# MMMM_Top.net
KiCad netlist of a schematic drawn in EAGLE
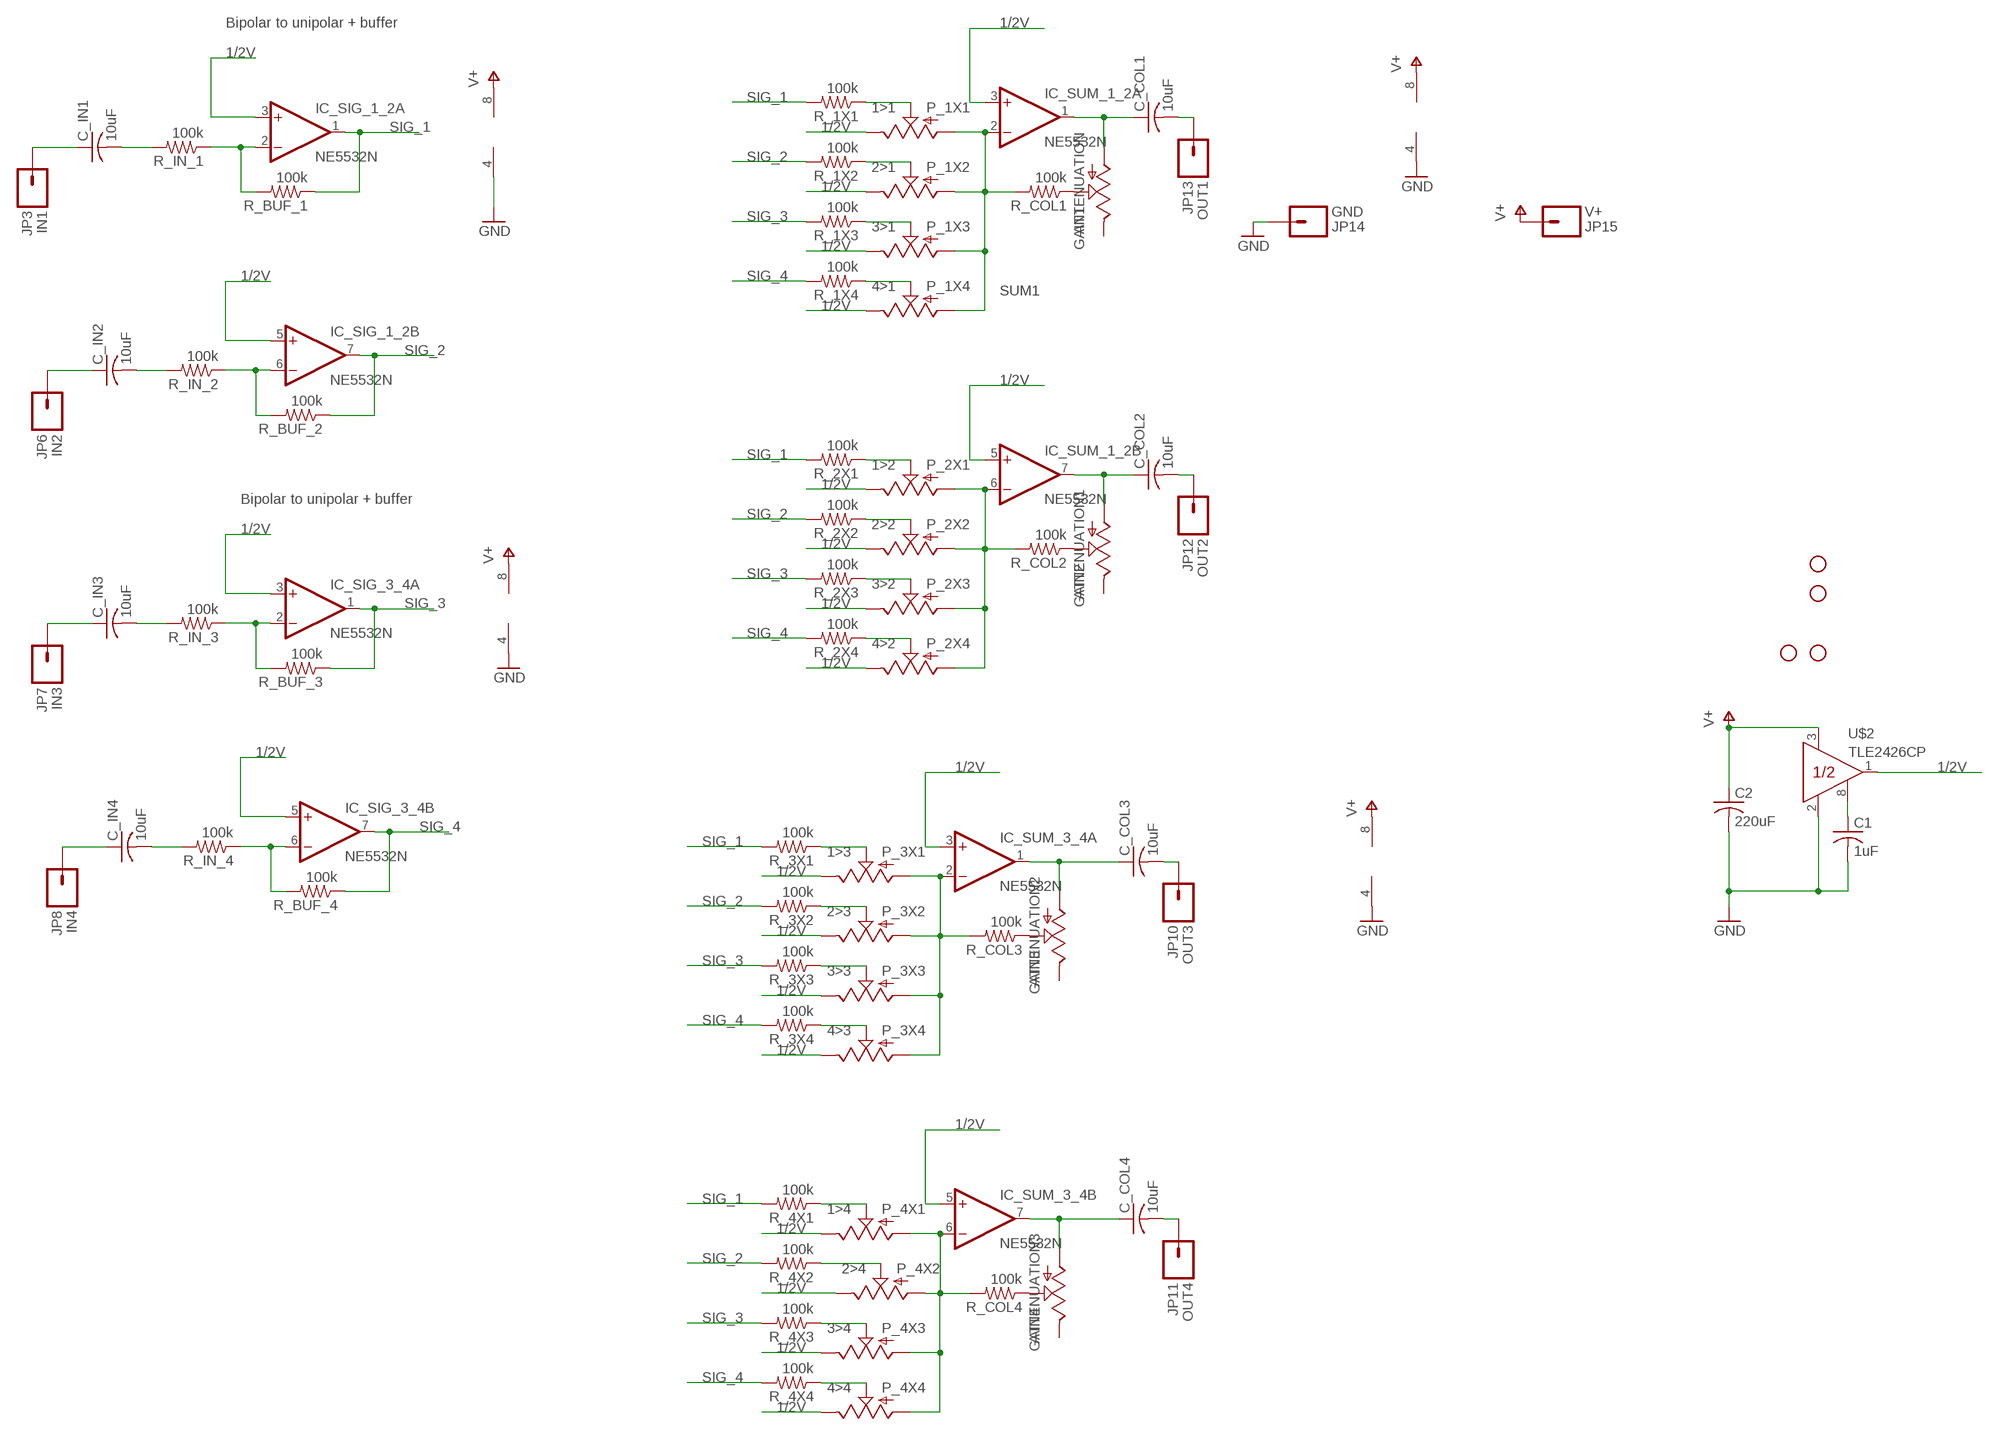
[diagram p0: schematic, sheet 1]

(export (version "E")
  (design (tool "Eeschema 10.0.6"))
  (components
    (comp (ref "ATTENUATION")
      (value "GAIN1")
      (footprint "eagle-import:TRIM_POT")
      (libsource (lib "eagle-import") (part "POTTRIM"))
    )
    (comp (ref "ATTENUATION1")
      (value "GAIN2")
      (footprint "eagle-import:TRIM_POT")
      (libsource (lib "eagle-import") (part "POTTRIM"))
    )
    (comp (ref "ATTENUATION2")
      (value "GAIN3")
      (footprint "eagle-import:TRIM_POT")
      (libsource (lib "eagle-import") (part "POTTRIM"))
    )
    (comp (ref "ATTENUATION3")
      (value "GAIN4")
      (footprint "eagle-import:TRIM_POT")
      (libsource (lib "eagle-import") (part "POTTRIM"))
    )
    (comp (ref "C1")
      (value "1uF")
      (footprint "eagle-import:C025-030X050")
      (libsource (lib "eagle-import") (part "C-US025-030X050"))
    )
    (comp (ref "C2")
      (value "220uF")
      (footprint "eagle-import:C050-075X075")
      (libsource (lib "eagle-import") (part "C-US050-075X075"))
    )
    (comp (ref "C_COL1")
      (value "10uF")
      (footprint "eagle-import:C025-025X050")
      (libsource (lib "eagle-import") (part "C-US025-025X050"))
    )
    (comp (ref "C_COL2")
      (value "10uF")
      (footprint "eagle-import:C025-025X050")
      (libsource (lib "eagle-import") (part "C-US025-025X050"))
    )
    (comp (ref "C_COL3")
      (value "10uF")
      (footprint "eagle-import:C025-025X050")
      (libsource (lib "eagle-import") (part "C-US025-025X050"))
    )
    (comp (ref "C_COL4")
      (value "10uF")
      (footprint "eagle-import:C025-025X050")
      (libsource (lib "eagle-import") (part "C-US025-025X050"))
    )
    (comp (ref "C_IN1")
      (value "10uF")
      (footprint "eagle-import:C025-025X050")
      (libsource (lib "eagle-import") (part "C-US025-025X050"))
    )
    (comp (ref "C_IN2")
      (value "10uF")
      (footprint "eagle-import:C025-025X050")
      (libsource (lib "eagle-import") (part "C-US025-025X050"))
    )
    (comp (ref "C_IN3")
      (value "10uF")
      (footprint "eagle-import:C025-025X050")
      (libsource (lib "eagle-import") (part "C-US025-025X050"))
    )
    (comp (ref "C_IN4")
      (value "10uF")
      (footprint "eagle-import:C025-025X050")
      (libsource (lib "eagle-import") (part "C-US025-025X050"))
    )
    (comp (ref "IC_SIG_1_2")
      (value "NE5532N")
      (footprint "eagle-import:DIL08")
      (libsource (lib "eagle-import") (part "NE5532N"))
    )
    (comp (ref "IC_SIG_3_4")
      (value "NE5532N")
      (footprint "eagle-import:DIL08")
      (libsource (lib "eagle-import") (part "NE5532N"))
    )
    (comp (ref "IC_SUM_1_2")
      (value "NE5532N")
      (footprint "eagle-import:DIL08")
      (libsource (lib "eagle-import") (part "NE5532N"))
    )
    (comp (ref "IC_SUM_3_4")
      (value "NE5532N")
      (footprint "eagle-import:DIL08")
      (libsource (lib "eagle-import") (part "NE5532N"))
    )
    (comp (ref "JP1")
      (value "STAND-OFF")
      (footprint "eagle-import:STAND-OFF")
      (libsource (lib "eagle-import") (part "STAND-OFF"))
    )
    (comp (ref "JP2")
      (value "STAND-OFF")
      (footprint "eagle-import:STAND-OFF")
      (libsource (lib "eagle-import") (part "STAND-OFF"))
    )
    (comp (ref "JP3")
      (value "IN1")
      (footprint "eagle-import:1X01_SIDE_NAME")
      (libsource (lib "eagle-import") (part "HEADER-1X1"))
    )
    (comp (ref "JP4")
      (value "STAND-OFF")
      (footprint "eagle-import:STAND-OFF")
      (libsource (lib "eagle-import") (part "STAND-OFF"))
    )
    (comp (ref "JP5")
      (value "STAND-OFF")
      (footprint "eagle-import:STAND-OFF")
      (libsource (lib "eagle-import") (part "STAND-OFF"))
    )
    (comp (ref "JP6")
      (value "IN2")
      (footprint "eagle-import:1X01_SIDE_NAME")
      (libsource (lib "eagle-import") (part "HEADER-1X1"))
    )
    (comp (ref "JP7")
      (value "IN3")
      (footprint "eagle-import:1X01_SIDE_NAME")
      (libsource (lib "eagle-import") (part "HEADER-1X1"))
    )
    (comp (ref "JP8")
      (value "IN4")
      (footprint "eagle-import:1X01_SIDE_NAME")
      (libsource (lib "eagle-import") (part "HEADER-1X1"))
    )
    (comp (ref "JP10")
      (value "OUT3")
      (footprint "eagle-import:1X01_SIDE_NAME")
      (libsource (lib "eagle-import") (part "HEADER-1X1"))
    )
    (comp (ref "JP11")
      (value "OUT4")
      (footprint "eagle-import:1X01_SIDE_NAME")
      (libsource (lib "eagle-import") (part "HEADER-1X1"))
    )
    (comp (ref "JP12")
      (value "OUT2")
      (footprint "eagle-import:1X01_SIDE_NAME")
      (libsource (lib "eagle-import") (part "HEADER-1X1"))
    )
    (comp (ref "JP13")
      (value "OUT1")
      (footprint "eagle-import:1X01_SIDE_NAME")
      (libsource (lib "eagle-import") (part "HEADER-1X1"))
    )
    (comp (ref "JP14")
      (value "GND")
      (footprint "eagle-import:1X01_SIDE_NAME")
      (libsource (lib "eagle-import") (part "HEADER-1X1"))
    )
    (comp (ref "JP15")
      (value "V+")
      (footprint "eagle-import:1X01_SIDE_NAME")
      (libsource (lib "eagle-import") (part "HEADER-1X1"))
    )
    (comp (ref "P_1X1")
      (value "1>1")
      (footprint "eagle-import:ALPS_POT")
      (libsource (lib "eagle-import") (part "POT"))
    )
    (comp (ref "P_1X2")
      (value "2>1")
      (footprint "eagle-import:ALPS_POT")
      (libsource (lib "eagle-import") (part "POT"))
    )
    (comp (ref "P_1X3")
      (value "3>1")
      (footprint "eagle-import:ALPS_POT")
      (libsource (lib "eagle-import") (part "POT"))
    )
    (comp (ref "P_1X4")
      (value "4>1")
      (footprint "eagle-import:ALPS_POT")
      (libsource (lib "eagle-import") (part "POT"))
    )
    (comp (ref "P_2X1")
      (value "1>2")
      (footprint "eagle-import:ALPS_POT")
      (libsource (lib "eagle-import") (part "POT"))
    )
    (comp (ref "P_2X2")
      (value "2>2")
      (footprint "eagle-import:ALPS_POT")
      (libsource (lib "eagle-import") (part "POT"))
    )
    (comp (ref "P_2X3")
      (value "3>2")
      (footprint "eagle-import:ALPS_POT")
      (libsource (lib "eagle-import") (part "POT"))
    )
    (comp (ref "P_2X4")
      (value "4>2")
      (footprint "eagle-import:ALPS_POT")
      (libsource (lib "eagle-import") (part "POT"))
    )
    (comp (ref "P_3X1")
      (value "1>3")
      (footprint "eagle-import:ALPS_POT")
      (libsource (lib "eagle-import") (part "POT"))
    )
    (comp (ref "P_3X2")
      (value "2>3")
      (footprint "eagle-import:ALPS_POT")
      (libsource (lib "eagle-import") (part "POT"))
    )
    (comp (ref "P_3X3")
      (value "3>3")
      (footprint "eagle-import:ALPS_POT")
      (libsource (lib "eagle-import") (part "POT"))
    )
    (comp (ref "P_3X4")
      (value "4>3")
      (footprint "eagle-import:ALPS_POT")
      (libsource (lib "eagle-import") (part "POT"))
    )
    (comp (ref "P_4X1")
      (value "1>4")
      (footprint "eagle-import:ALPS_POT")
      (libsource (lib "eagle-import") (part "POT"))
    )
    (comp (ref "P_4X2")
      (value "2>4")
      (footprint "eagle-import:ALPS_POT")
      (libsource (lib "eagle-import") (part "POT"))
    )
    (comp (ref "P_4X3")
      (value "3>4")
      (footprint "eagle-import:ALPS_POT")
      (libsource (lib "eagle-import") (part "POT"))
    )
    (comp (ref "P_4X4")
      (value "4>4")
      (footprint "eagle-import:ALPS_POT")
      (libsource (lib "eagle-import") (part "POT"))
    )
    (comp (ref "R_1X1")
      (value "100k")
      (footprint "eagle-import:0204_5")
      (libsource (lib "eagle-import") (part "R-US_0204/5"))
    )
    (comp (ref "R_1X2")
      (value "100k")
      (footprint "eagle-import:0204_5")
      (libsource (lib "eagle-import") (part "R-US_0204/5"))
    )
    (comp (ref "R_1X3")
      (value "100k")
      (footprint "eagle-import:0204_5")
      (libsource (lib "eagle-import") (part "R-US_0204/5"))
    )
    (comp (ref "R_1X4")
      (value "100k")
      (footprint "eagle-import:0204_5")
      (libsource (lib "eagle-import") (part "R-US_0204/5"))
    )
    (comp (ref "R_2X1")
      (value "100k")
      (footprint "eagle-import:0204_5")
      (libsource (lib "eagle-import") (part "R-US_0204/5"))
    )
    (comp (ref "R_2X2")
      (value "100k")
      (footprint "eagle-import:0204_5")
      (libsource (lib "eagle-import") (part "R-US_0204/5"))
    )
    (comp (ref "R_2X3")
      (value "100k")
      (footprint "eagle-import:0204_5")
      (libsource (lib "eagle-import") (part "R-US_0204/5"))
    )
    (comp (ref "R_2X4")
      (value "100k")
      (footprint "eagle-import:0204_5")
      (libsource (lib "eagle-import") (part "R-US_0204/5"))
    )
    (comp (ref "R_3X1")
      (value "100k")
      (footprint "eagle-import:0204_5")
      (libsource (lib "eagle-import") (part "R-US_0204/5"))
    )
    (comp (ref "R_3X2")
      (value "100k")
      (footprint "eagle-import:0204_5")
      (libsource (lib "eagle-import") (part "R-US_0204/5"))
    )
    (comp (ref "R_3X3")
      (value "100k")
      (footprint "eagle-import:0204_5")
      (libsource (lib "eagle-import") (part "R-US_0204/5"))
    )
    (comp (ref "R_3X4")
      (value "100k")
      (footprint "eagle-import:0204_5")
      (libsource (lib "eagle-import") (part "R-US_0204/5"))
    )
    (comp (ref "R_4X1")
      (value "100k")
      (footprint "eagle-import:0204_5")
      (libsource (lib "eagle-import") (part "R-US_0204/5"))
    )
    (comp (ref "R_4X2")
      (value "100k")
      (footprint "eagle-import:0204_5")
      (libsource (lib "eagle-import") (part "R-US_0204/5"))
    )
    (comp (ref "R_4X3")
      (value "100k")
      (footprint "eagle-import:0204_5")
      (libsource (lib "eagle-import") (part "R-US_0204/5"))
    )
    (comp (ref "R_4X4")
      (value "100k")
      (footprint "eagle-import:0204_5")
      (libsource (lib "eagle-import") (part "R-US_0204/5"))
    )
    (comp (ref "R_BUF_1")
      (value "100k")
      (footprint "eagle-import:0204_5")
      (libsource (lib "eagle-import") (part "R-US_0204/5"))
    )
    (comp (ref "R_BUF_2")
      (value "100k")
      (footprint "eagle-import:0204_5")
      (libsource (lib "eagle-import") (part "R-US_0204/5"))
    )
    (comp (ref "R_BUF_3")
      (value "100k")
      (footprint "eagle-import:0204_5")
      (libsource (lib "eagle-import") (part "R-US_0204/5"))
    )
    (comp (ref "R_BUF_4")
      (value "100k")
      (footprint "eagle-import:0204_5")
      (libsource (lib "eagle-import") (part "R-US_0204/5"))
    )
    (comp (ref "R_COL1")
      (value "100k")
      (footprint "eagle-import:0204_5")
      (libsource (lib "eagle-import") (part "R-US_0204/5"))
    )
    (comp (ref "R_COL2")
      (value "100k")
      (footprint "eagle-import:0204_5")
      (libsource (lib "eagle-import") (part "R-US_0204/5"))
    )
    (comp (ref "R_COL3")
      (value "100k")
      (footprint "eagle-import:0204_5")
      (libsource (lib "eagle-import") (part "R-US_0204/5"))
    )
    (comp (ref "R_COL4")
      (value "100k")
      (footprint "eagle-import:0204_5")
      (libsource (lib "eagle-import") (part "R-US_0204/5"))
    )
    (comp (ref "R_IN_1")
      (value "100k")
      (footprint "eagle-import:0204_5")
      (libsource (lib "eagle-import") (part "R-US_0204/5"))
    )
    (comp (ref "R_IN_2")
      (value "100k")
      (footprint "eagle-import:0204_5")
      (libsource (lib "eagle-import") (part "R-US_0204/5"))
    )
    (comp (ref "R_IN_3")
      (value "100k")
      (footprint "eagle-import:0204_5")
      (libsource (lib "eagle-import") (part "R-US_0204/5"))
    )
    (comp (ref "R_IN_4")
      (value "100k")
      (footprint "eagle-import:0204_5")
      (libsource (lib "eagle-import") (part "R-US_0204/5"))
    )
    (comp (ref "U$2")
      (value "TLE2426CP")
      (footprint "eagle-import:DIP-8")
      (libsource (lib "eagle-import") (part "TLE2426PC"))
    )
  )
  (nets
    (net (code "1") (name "/1{slash}2V") (class "Default")
      (node (ref "IC_SIG_1_2") (pin "3") (pinfunction "+IN_3") (pintype "input"))
      (node (ref "IC_SIG_1_2") (pin "5") (pinfunction "+IN_5") (pintype "input"))
      (node (ref "IC_SIG_3_4") (pin "3") (pinfunction "+IN_3") (pintype "input"))
      (node (ref "IC_SIG_3_4") (pin "5") (pinfunction "+IN_5") (pintype "input"))
      (node (ref "IC_SUM_1_2") (pin "3") (pinfunction "+IN_3") (pintype "input"))
      (node (ref "IC_SUM_1_2") (pin "5") (pinfunction "+IN_5") (pintype "input"))
      (node (ref "IC_SUM_3_4") (pin "3") (pinfunction "+IN_3") (pintype "input"))
      (node (ref "IC_SUM_3_4") (pin "5") (pinfunction "+IN_5") (pintype "input"))
      (node (ref "P_1X1") (pin "P$1") (pinfunction "E_P$1") (pintype "passive"))
      (node (ref "P_1X2") (pin "P$1") (pinfunction "E_P$1") (pintype "passive"))
      (node (ref "P_1X3") (pin "P$1") (pinfunction "E_P$1") (pintype "passive"))
      (node (ref "P_1X4") (pin "P$1") (pinfunction "E_P$1") (pintype "passive"))
      (node (ref "P_2X1") (pin "P$1") (pinfunction "E_P$1") (pintype "passive"))
      (node (ref "P_2X2") (pin "P$1") (pinfunction "E_P$1") (pintype "passive"))
      (node (ref "P_2X3") (pin "P$1") (pinfunction "E_P$1") (pintype "passive"))
      (node (ref "P_2X4") (pin "P$1") (pinfunction "E_P$1") (pintype "passive"))
      (node (ref "P_3X1") (pin "P$1") (pinfunction "E_P$1") (pintype "passive"))
      (node (ref "P_3X2") (pin "P$1") (pinfunction "E_P$1") (pintype "passive"))
      (node (ref "P_3X3") (pin "P$1") (pinfunction "E_P$1") (pintype "passive"))
      (node (ref "P_3X4") (pin "P$1") (pinfunction "E_P$1") (pintype "passive"))
      (node (ref "P_4X1") (pin "P$1") (pinfunction "E_P$1") (pintype "passive"))
      (node (ref "P_4X2") (pin "P$1") (pinfunction "E_P$1") (pintype "passive"))
      (node (ref "P_4X3") (pin "P$1") (pinfunction "E_P$1") (pintype "passive"))
      (node (ref "P_4X4") (pin "P$1") (pinfunction "E_P$1") (pintype "passive"))
      (node (ref "U$2") (pin "1") (pinfunction "OUT_1") (pintype "passive"))
    )
    (net (code "2") (name "/SIG_1") (class "Default")
      (node (ref "IC_SIG_1_2") (pin "1") (pinfunction "OUT_1") (pintype "output"))
      (node (ref "R_1X1") (pin "2") (pinfunction "2_2") (pintype "passive"))
      (node (ref "R_2X1") (pin "2") (pinfunction "2_2") (pintype "passive"))
      (node (ref "R_3X1") (pin "2") (pinfunction "2_2") (pintype "passive"))
      (node (ref "R_4X1") (pin "2") (pinfunction "2_2") (pintype "passive"))
      (node (ref "R_BUF_1") (pin "1") (pinfunction "1_1") (pintype "passive"))
    )
    (net (code "3") (name "/SIG_2") (class "Default")
      (node (ref "IC_SIG_1_2") (pin "7") (pinfunction "OUT_7") (pintype "output"))
      (node (ref "R_1X2") (pin "2") (pinfunction "2_2") (pintype "passive"))
      (node (ref "R_2X2") (pin "2") (pinfunction "2_2") (pintype "passive"))
      (node (ref "R_3X2") (pin "2") (pinfunction "2_2") (pintype "passive"))
      (node (ref "R_4X2") (pin "2") (pinfunction "2_2") (pintype "passive"))
      (node (ref "R_BUF_2") (pin "1") (pinfunction "1_1") (pintype "passive"))
    )
    (net (code "4") (name "/SIG_3") (class "Default")
      (node (ref "IC_SIG_3_4") (pin "1") (pinfunction "OUT_1") (pintype "output"))
      (node (ref "R_1X3") (pin "2") (pinfunction "2_2") (pintype "passive"))
      (node (ref "R_2X3") (pin "2") (pinfunction "2_2") (pintype "passive"))
      (node (ref "R_3X3") (pin "2") (pinfunction "2_2") (pintype "passive"))
      (node (ref "R_4X3") (pin "2") (pinfunction "2_2") (pintype "passive"))
      (node (ref "R_BUF_3") (pin "1") (pinfunction "1_1") (pintype "passive"))
    )
    (net (code "5") (name "/SIG_4") (class "Default")
      (node (ref "IC_SIG_3_4") (pin "7") (pinfunction "OUT_7") (pintype "output"))
      (node (ref "R_1X4") (pin "2") (pinfunction "2_2") (pintype "passive"))
      (node (ref "R_2X4") (pin "2") (pinfunction "2_2") (pintype "passive"))
      (node (ref "R_3X4") (pin "2") (pinfunction "2_2") (pintype "passive"))
      (node (ref "R_4X4") (pin "2") (pinfunction "2_2") (pintype "passive"))
      (node (ref "R_BUF_4") (pin "1") (pinfunction "1_1") (pintype "passive"))
    )
    (net (code "6") (name "/SUM1") (class "Default")
      (node (ref "IC_SUM_1_2") (pin "2") (pinfunction "-IN_2") (pintype "input"))
      (node (ref "P_1X1") (pin "P$3") (pinfunction "A_P$3") (pintype "passive"))
      (node (ref "P_1X2") (pin "P$3") (pinfunction "A_P$3") (pintype "passive"))
      (node (ref "P_1X3") (pin "P$3") (pinfunction "A_P$3") (pintype "passive"))
      (node (ref "P_1X4") (pin "P$3") (pinfunction "A_P$3") (pintype "passive"))
      (node (ref "R_COL1") (pin "2") (pinfunction "2_2") (pintype "passive"))
    )
    (net (code "7") (name "GND") (class "Default")
      (node (ref "C1") (pin "2") (pinfunction "2_2") (pintype "passive"))
      (node (ref "C2") (pin "2") (pinfunction "2_2") (pintype "passive"))
      (node (ref "IC_SIG_1_2") (pin "4") (pinfunction "V-_4") (pintype "power_in"))
      (node (ref "IC_SIG_3_4") (pin "4") (pinfunction "V-_4") (pintype "power_in"))
      (node (ref "IC_SUM_1_2") (pin "4") (pinfunction "V-_4") (pintype "power_in"))
      (node (ref "IC_SUM_3_4") (pin "4") (pinfunction "V-_4") (pintype "power_in"))
      (node (ref "JP14") (pin "1") (pinfunction "1_1") (pintype "passive"))
      (node (ref "U$2") (pin "2") (pinfunction "COM_2") (pintype "passive"))
    )
    (net (code "8") (name "Net-(ATTENUATION-A)") (class "Default")
      (node (ref "ATTENUATION") (pin "3") (pinfunction "A_3") (pintype "passive"))
      (node (ref "C_COL1") (pin "1") (pinfunction "1_1") (pintype "passive"))
      (node (ref "IC_SUM_1_2") (pin "1") (pinfunction "OUT_1") (pintype "output"))
    )
    (net (code "9") (name "Net-(ATTENUATION-S)") (class "Default")
      (node (ref "ATTENUATION") (pin "1") (pinfunction "S_1") (pintype "passive"))
      (node (ref "R_COL1") (pin "1") (pinfunction "1_1") (pintype "passive"))
    )
    (net (code "10") (name "Net-(ATTENUATION1-A)") (class "Default")
      (node (ref "ATTENUATION1") (pin "3") (pinfunction "A_3") (pintype "passive"))
      (node (ref "C_COL2") (pin "1") (pinfunction "1_1") (pintype "passive"))
      (node (ref "IC_SUM_1_2") (pin "7") (pinfunction "OUT_7") (pintype "output"))
    )
    (net (code "11") (name "Net-(ATTENUATION1-S)") (class "Default")
      (node (ref "ATTENUATION1") (pin "1") (pinfunction "S_1") (pintype "passive"))
      (node (ref "R_COL2") (pin "1") (pinfunction "1_1") (pintype "passive"))
    )
    (net (code "12") (name "Net-(ATTENUATION2-A)") (class "Default")
      (node (ref "ATTENUATION2") (pin "3") (pinfunction "A_3") (pintype "passive"))
      (node (ref "C_COL3") (pin "1") (pinfunction "1_1") (pintype "passive"))
      (node (ref "IC_SUM_3_4") (pin "1") (pinfunction "OUT_1") (pintype "output"))
    )
    (net (code "13") (name "Net-(ATTENUATION2-S)") (class "Default")
      (node (ref "ATTENUATION2") (pin "1") (pinfunction "S_1") (pintype "passive"))
      (node (ref "R_COL3") (pin "1") (pinfunction "1_1") (pintype "passive"))
    )
    (net (code "14") (name "Net-(ATTENUATION3-A)") (class "Default")
      (node (ref "ATTENUATION3") (pin "3") (pinfunction "A_3") (pintype "passive"))
      (node (ref "C_COL4") (pin "1") (pinfunction "1_1") (pintype "passive"))
      (node (ref "IC_SUM_3_4") (pin "7") (pinfunction "OUT_7") (pintype "output"))
    )
    (net (code "15") (name "Net-(ATTENUATION3-S)") (class "Default")
      (node (ref "ATTENUATION3") (pin "1") (pinfunction "S_1") (pintype "passive"))
      (node (ref "R_COL4") (pin "1") (pinfunction "1_1") (pintype "passive"))
    )
    (net (code "16") (name "Net-(C_COL1-Pad2)") (class "Default")
      (node (ref "C_COL1") (pin "2") (pinfunction "2_2") (pintype "passive"))
      (node (ref "JP13") (pin "1") (pinfunction "1_1") (pintype "passive"))
    )
    (net (code "17") (name "Net-(C_COL2-Pad2)") (class "Default")
      (node (ref "C_COL2") (pin "2") (pinfunction "2_2") (pintype "passive"))
      (node (ref "JP12") (pin "1") (pinfunction "1_1") (pintype "passive"))
    )
    (net (code "18") (name "Net-(C_COL3-Pad2)") (class "Default")
      (node (ref "C_COL3") (pin "2") (pinfunction "2_2") (pintype "passive"))
      (node (ref "JP10") (pin "1") (pinfunction "1_1") (pintype "passive"))
    )
    (net (code "19") (name "Net-(C_COL4-Pad2)") (class "Default")
      (node (ref "C_COL4") (pin "2") (pinfunction "2_2") (pintype "passive"))
      (node (ref "JP11") (pin "1") (pinfunction "1_1") (pintype "passive"))
    )
    (net (code "20") (name "Net-(C_IN1-Pad1)") (class "Default")
      (node (ref "C_IN1") (pin "1") (pinfunction "1_1") (pintype "passive"))
      (node (ref "JP3") (pin "1") (pinfunction "1_1") (pintype "passive"))
    )
    (net (code "21") (name "Net-(C_IN1-Pad2)") (class "Default")
      (node (ref "C_IN1") (pin "2") (pinfunction "2_2") (pintype "passive"))
      (node (ref "R_IN_1") (pin "2") (pinfunction "2_2") (pintype "passive"))
    )
    (net (code "22") (name "Net-(C_IN2-Pad1)") (class "Default")
      (node (ref "C_IN2") (pin "1") (pinfunction "1_1") (pintype "passive"))
      (node (ref "JP6") (pin "1") (pinfunction "1_1") (pintype "passive"))
    )
    (net (code "23") (name "Net-(C_IN2-Pad2)") (class "Default")
      (node (ref "C_IN2") (pin "2") (pinfunction "2_2") (pintype "passive"))
      (node (ref "R_IN_2") (pin "2") (pinfunction "2_2") (pintype "passive"))
    )
    (net (code "24") (name "Net-(C_IN3-Pad1)") (class "Default")
      (node (ref "C_IN3") (pin "1") (pinfunction "1_1") (pintype "passive"))
      (node (ref "JP7") (pin "1") (pinfunction "1_1") (pintype "passive"))
    )
    (net (code "25") (name "Net-(C_IN3-Pad2)") (class "Default")
      (node (ref "C_IN3") (pin "2") (pinfunction "2_2") (pintype "passive"))
      (node (ref "R_IN_3") (pin "2") (pinfunction "2_2") (pintype "passive"))
    )
    (net (code "26") (name "Net-(C_IN4-Pad1)") (class "Default")
      (node (ref "C_IN4") (pin "1") (pinfunction "1_1") (pintype "passive"))
      (node (ref "JP8") (pin "1") (pinfunction "1_1") (pintype "passive"))
    )
    (net (code "27") (name "Net-(C_IN4-Pad2)") (class "Default")
      (node (ref "C_IN4") (pin "2") (pinfunction "2_2") (pintype "passive"))
      (node (ref "R_IN_4") (pin "2") (pinfunction "2_2") (pintype "passive"))
    )
    (net (code "28") (name "Net-(IC_SIG_1_2A--IN)") (class "Default")
      (node (ref "IC_SIG_1_2") (pin "2") (pinfunction "-IN_2") (pintype "input"))
      (node (ref "R_BUF_1") (pin "2") (pinfunction "2_2") (pintype "passive"))
      (node (ref "R_IN_1") (pin "1") (pinfunction "1_1") (pintype "passive"))
    )
    (net (code "29") (name "Net-(IC_SIG_1_2B--IN)") (class "Default")
      (node (ref "IC_SIG_1_2") (pin "6") (pinfunction "-IN_6") (pintype "input"))
      (node (ref "R_BUF_2") (pin "2") (pinfunction "2_2") (pintype "passive"))
      (node (ref "R_IN_2") (pin "1") (pinfunction "1_1") (pintype "passive"))
    )
    (net (code "30") (name "Net-(IC_SIG_3_4A--IN)") (class "Default")
      (node (ref "IC_SIG_3_4") (pin "2") (pinfunction "-IN_2") (pintype "input"))
      (node (ref "R_BUF_3") (pin "2") (pinfunction "2_2") (pintype "passive"))
      (node (ref "R_IN_3") (pin "1") (pinfunction "1_1") (pintype "passive"))
    )
    (net (code "31") (name "Net-(IC_SIG_3_4B--IN)") (class "Default")
      (node (ref "IC_SIG_3_4") (pin "6") (pinfunction "-IN_6") (pintype "input"))
      (node (ref "R_BUF_4") (pin "2") (pinfunction "2_2") (pintype "passive"))
      (node (ref "R_IN_4") (pin "1") (pinfunction "1_1") (pintype "passive"))
    )
    (net (code "32") (name "Net-(IC_SUM_1_2B--IN)") (class "Default")
      (node (ref "IC_SUM_1_2") (pin "6") (pinfunction "-IN_6") (pintype "input"))
      (node (ref "P_2X1") (pin "P$3") (pinfunction "A_P$3") (pintype "passive"))
      (node (ref "P_2X2") (pin "P$3") (pinfunction "A_P$3") (pintype "passive"))
      (node (ref "P_2X3") (pin "P$3") (pinfunction "A_P$3") (pintype "passive"))
      (node (ref "P_2X4") (pin "P$3") (pinfunction "A_P$3") (pintype "passive"))
      (node (ref "R_COL2") (pin "2") (pinfunction "2_2") (pintype "passive"))
    )
    (net (code "33") (name "Net-(IC_SUM_3_4A--IN)") (class "Default")
      (node (ref "IC_SUM_3_4") (pin "2") (pinfunction "-IN_2") (pintype "input"))
      (node (ref "P_3X1") (pin "P$3") (pinfunction "A_P$3") (pintype "passive"))
      (node (ref "P_3X2") (pin "P$3") (pinfunction "A_P$3") (pintype "passive"))
      (node (ref "P_3X3") (pin "P$3") (pinfunction "A_P$3") (pintype "passive"))
      (node (ref "P_3X4") (pin "P$3") (pinfunction "A_P$3") (pintype "passive"))
      (node (ref "R_COL3") (pin "2") (pinfunction "2_2") (pintype "passive"))
    )
    (net (code "34") (name "Net-(IC_SUM_3_4B--IN)") (class "Default")
      (node (ref "IC_SUM_3_4") (pin "6") (pinfunction "-IN_6") (pintype "input"))
      (node (ref "P_4X1") (pin "P$3") (pinfunction "A_P$3") (pintype "passive"))
      (node (ref "P_4X2") (pin "P$3") (pinfunction "A_P$3") (pintype "passive"))
      (node (ref "P_4X3") (pin "P$3") (pinfunction "A_P$3") (pintype "passive"))
      (node (ref "P_4X4") (pin "P$3") (pinfunction "A_P$3") (pintype "passive"))
      (node (ref "R_COL4") (pin "2") (pinfunction "2_2") (pintype "passive"))
    )
    (net (code "35") (name "Net-(P_1X1-S)") (class "Default")
      (node (ref "P_1X1") (pin "P$2") (pinfunction "S_P$2") (pintype "passive"))
      (node (ref "R_1X1") (pin "1") (pinfunction "1_1") (pintype "passive"))
    )
    (net (code "36") (name "Net-(P_1X2-S)") (class "Default")
      (node (ref "P_1X2") (pin "P$2") (pinfunction "S_P$2") (pintype "passive"))
      (node (ref "R_1X2") (pin "1") (pinfunction "1_1") (pintype "passive"))
    )
    (net (code "37") (name "Net-(P_1X3-S)") (class "Default")
      (node (ref "P_1X3") (pin "P$2") (pinfunction "S_P$2") (pintype "passive"))
      (node (ref "R_1X3") (pin "1") (pinfunction "1_1") (pintype "passive"))
    )
    (net (code "38") (name "Net-(P_1X4-S)") (class "Default")
      (node (ref "P_1X4") (pin "P$2") (pinfunction "S_P$2") (pintype "passive"))
      (node (ref "R_1X4") (pin "1") (pinfunction "1_1") (pintype "passive"))
    )
    (net (code "39") (name "Net-(P_2X1-S)") (class "Default")
      (node (ref "P_2X1") (pin "P$2") (pinfunction "S_P$2") (pintype "passive"))
      (node (ref "R_2X1") (pin "1") (pinfunction "1_1") (pintype "passive"))
    )
    (net (code "40") (name "Net-(P_2X2-S)") (class "Default")
      (node (ref "P_2X2") (pin "P$2") (pinfunction "S_P$2") (pintype "passive"))
      (node (ref "R_2X2") (pin "1") (pinfunction "1_1") (pintype "passive"))
    )
    (net (code "41") (name "Net-(P_2X3-S)") (class "Default")
      (node (ref "P_2X3") (pin "P$2") (pinfunction "S_P$2") (pintype "passive"))
      (node (ref "R_2X3") (pin "1") (pinfunction "1_1") (pintype "passive"))
    )
    (net (code "42") (name "Net-(P_2X4-S)") (class "Default")
      (node (ref "P_2X4") (pin "P$2") (pinfunction "S_P$2") (pintype "passive"))
      (node (ref "R_2X4") (pin "1") (pinfunction "1_1") (pintype "passive"))
    )
    (net (code "43") (name "Net-(P_3X1-S)") (class "Default")
      (node (ref "P_3X1") (pin "P$2") (pinfunction "S_P$2") (pintype "passive"))
      (node (ref "R_3X1") (pin "1") (pinfunction "1_1") (pintype "passive"))
    )
    (net (code "44") (name "Net-(P_3X2-S)") (class "Default")
      (node (ref "P_3X2") (pin "P$2") (pinfunction "S_P$2") (pintype "passive"))
      (node (ref "R_3X2") (pin "1") (pinfunction "1_1") (pintype "passive"))
    )
    (net (code "45") (name "Net-(P_3X3-S)") (class "Default")
      (node (ref "P_3X3") (pin "P$2") (pinfunction "S_P$2") (pintype "passive"))
      (node (ref "R_3X3") (pin "1") (pinfunction "1_1") (pintype "passive"))
    )
    (net (code "46") (name "Net-(P_3X4-S)") (class "Default")
      (node (ref "P_3X4") (pin "P$2") (pinfunction "S_P$2") (pintype "passive"))
      (node (ref "R_3X4") (pin "1") (pinfunction "1_1") (pintype "passive"))
    )
    (net (code "47") (name "Net-(P_4X1-S)") (class "Default")
      (node (ref "P_4X1") (pin "P$2") (pinfunction "S_P$2") (pintype "passive"))
      (node (ref "R_4X1") (pin "1") (pinfunction "1_1") (pintype "passive"))
    )
    (net (code "48") (name "Net-(P_4X2-S)") (class "Default")
      (node (ref "P_4X2") (pin "P$2") (pinfunction "S_P$2") (pintype "passive"))
      (node (ref "R_4X2") (pin "1") (pinfunction "1_1") (pintype "passive"))
    )
    (net (code "49") (name "Net-(P_4X3-S)") (class "Default")
      (node (ref "P_4X3") (pin "P$2") (pinfunction "S_P$2") (pintype "passive"))
      (node (ref "R_4X3") (pin "1") (pinfunction "1_1") (pintype "passive"))
    )
    (net (code "50") (name "Net-(P_4X4-S)") (class "Default")
      (node (ref "P_4X4") (pin "P$2") (pinfunction "S_P$2") (pintype "passive"))
      (node (ref "R_4X4") (pin "1") (pinfunction "1_1") (pintype "passive"))
    )
    (net (code "51") (name "Net-(U$2-NR)") (class "Default")
      (node (ref "C1") (pin "1") (pinfunction "1_1") (pintype "passive"))
      (node (ref "U$2") (pin "8") (pinfunction "NR_8") (pintype "passive"))
    )
    (net (code "52") (name "V+") (class "Default")
      (node (ref "C2") (pin "1") (pinfunction "1_1") (pintype "passive"))
      (node (ref "IC_SIG_1_2") (pin "8") (pinfunction "V+_8") (pintype "power_in"))
      (node (ref "IC_SIG_3_4") (pin "8") (pinfunction "V+_8") (pintype "power_in"))
      (node (ref "IC_SUM_1_2") (pin "8") (pinfunction "V+_8") (pintype "power_in"))
      (node (ref "IC_SUM_3_4") (pin "8") (pinfunction "V+_8") (pintype "power_in"))
      (node (ref "JP15") (pin "1") (pinfunction "1_1") (pintype "passive"))
      (node (ref "U$2") (pin "3") (pinfunction "IN_3") (pintype "passive"))
    )
    (net (code "53") (name "unconnected-(ATTENUATION-E-Pad2)") (class "Default")
      (node (ref "ATTENUATION") (pin "2") (pinfunction "E_2") (pintype "passive"))
    )
    (net (code "54") (name "unconnected-(ATTENUATION1-E-Pad2)") (class "Default")
      (node (ref "ATTENUATION1") (pin "2") (pinfunction "E_2") (pintype "passive"))
    )
    (net (code "55") (name "unconnected-(ATTENUATION2-E-Pad2)") (class "Default")
      (node (ref "ATTENUATION2") (pin "2") (pinfunction "E_2") (pintype "passive"))
    )
    (net (code "56") (name "unconnected-(ATTENUATION3-E-Pad2)") (class "Default")
      (node (ref "ATTENUATION3") (pin "2") (pinfunction "E_2") (pintype "passive"))
    )
  )
)
